# 5-leds.net
KiCad netlist of a schematic drawn in EAGLE
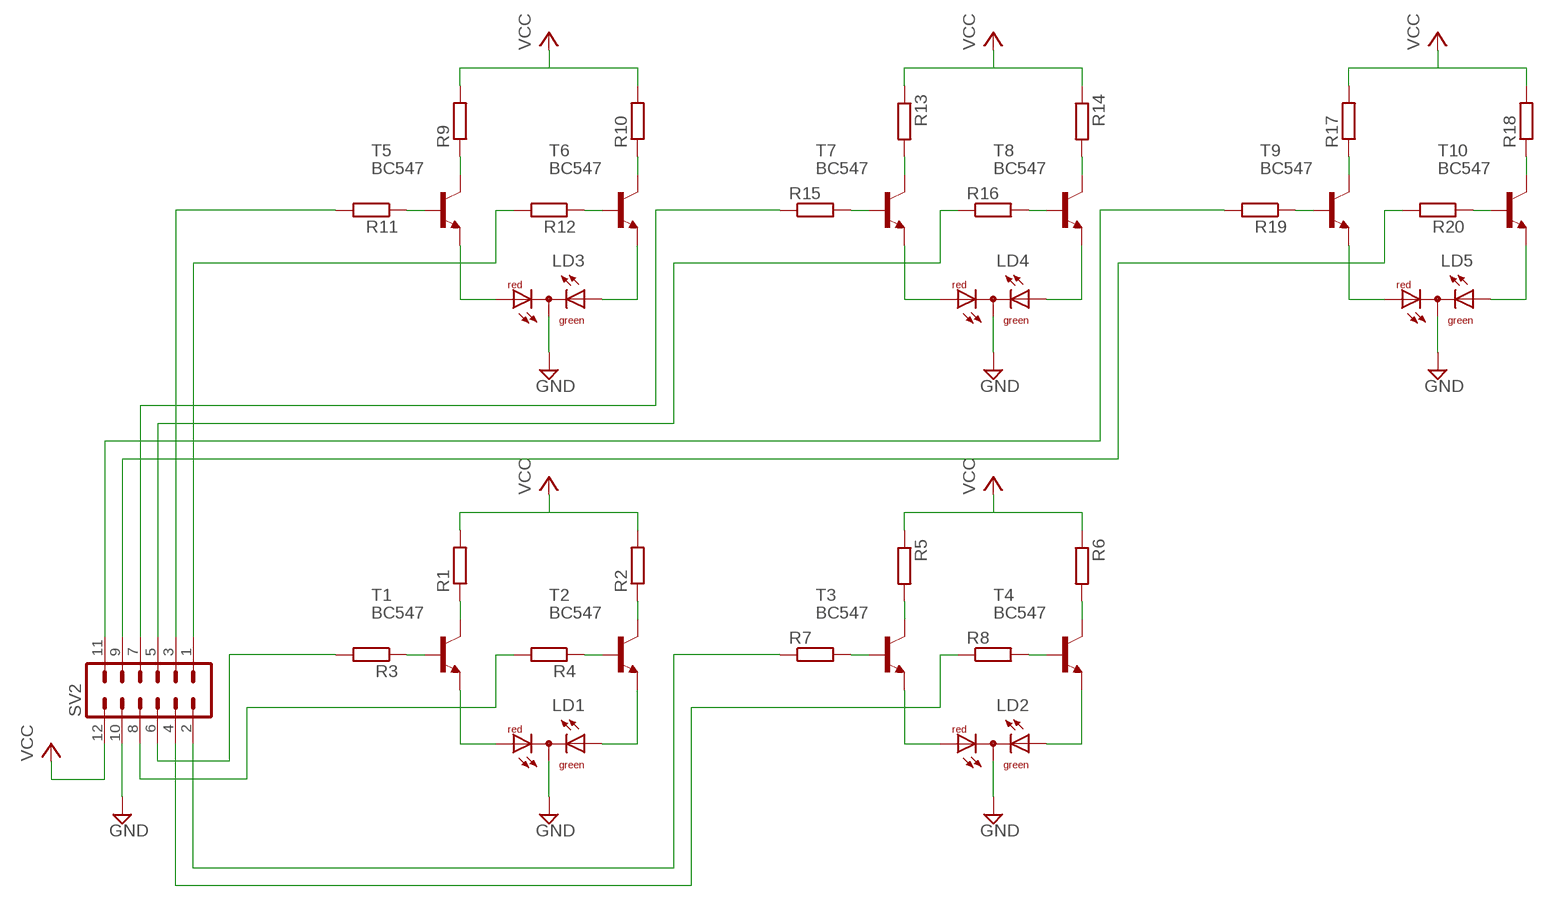
[diagram p0: schematic, sheet 1]

(export (version "E")
  (design (tool "Eeschema 10.0.6"))
  (components
    (comp (ref "LD1")
      (value "DUOLED-RG-C")
      (footprint "eagle-import:DUOLED-C-5MM")
      (libsource (lib "eagle-import") (part "DUOLED-RG-C"))
    )
    (comp (ref "LD2")
      (value "DUOLED-RG-C")
      (footprint "eagle-import:DUOLED-C-5MM")
      (libsource (lib "eagle-import") (part "DUOLED-RG-C"))
    )
    (comp (ref "LD3")
      (value "DUOLED-RG-C")
      (footprint "eagle-import:DUOLED-C-5MM")
      (libsource (lib "eagle-import") (part "DUOLED-RG-C"))
    )
    (comp (ref "LD4")
      (value "DUOLED-RG-C")
      (footprint "eagle-import:DUOLED-C-5MM")
      (libsource (lib "eagle-import") (part "DUOLED-RG-C"))
    )
    (comp (ref "LD5")
      (value "DUOLED-RG-C")
      (footprint "eagle-import:DUOLED-C-5MM")
      (libsource (lib "eagle-import") (part "DUOLED-RG-C"))
    )
    (comp (ref "R1")
      (value "R-EU_0207/7")
      (footprint "eagle-import:0207_7")
      (libsource (lib "eagle-import") (part "R-EU_0207/7"))
    )
    (comp (ref "R2")
      (value "R-EU_0207/7")
      (footprint "eagle-import:0207_7")
      (libsource (lib "eagle-import") (part "R-EU_0207/7"))
    )
    (comp (ref "R3")
      (value "R-EU_0207/7")
      (footprint "eagle-import:0207_7")
      (libsource (lib "eagle-import") (part "R-EU_0207/7"))
    )
    (comp (ref "R4")
      (value "R-EU_0207/7")
      (footprint "eagle-import:0207_7")
      (libsource (lib "eagle-import") (part "R-EU_0207/7"))
    )
    (comp (ref "R5")
      (value "R-EU_0207/7")
      (footprint "eagle-import:0207_7")
      (libsource (lib "eagle-import") (part "R-EU_0207/7"))
    )
    (comp (ref "R6")
      (value "R-EU_0207/7")
      (footprint "eagle-import:0207_7")
      (libsource (lib "eagle-import") (part "R-EU_0207/7"))
    )
    (comp (ref "R7")
      (value "R-EU_0207/7")
      (footprint "eagle-import:0207_7")
      (libsource (lib "eagle-import") (part "R-EU_0207/7"))
    )
    (comp (ref "R8")
      (value "R-EU_0207/7")
      (footprint "eagle-import:0207_7")
      (libsource (lib "eagle-import") (part "R-EU_0207/7"))
    )
    (comp (ref "R9")
      (value "R-EU_0207/7")
      (footprint "eagle-import:0207_7")
      (libsource (lib "eagle-import") (part "R-EU_0207/7"))
    )
    (comp (ref "R10")
      (value "R-EU_0207/7")
      (footprint "eagle-import:0207_7")
      (libsource (lib "eagle-import") (part "R-EU_0207/7"))
    )
    (comp (ref "R11")
      (value "R-EU_0207/7")
      (footprint "eagle-import:0207_7")
      (libsource (lib "eagle-import") (part "R-EU_0207/7"))
    )
    (comp (ref "R12")
      (value "R-EU_0207/7")
      (footprint "eagle-import:0207_7")
      (libsource (lib "eagle-import") (part "R-EU_0207/7"))
    )
    (comp (ref "R13")
      (value "R-EU_0207/7")
      (footprint "eagle-import:0207_7")
      (libsource (lib "eagle-import") (part "R-EU_0207/7"))
    )
    (comp (ref "R14")
      (value "R-EU_0207/7")
      (footprint "eagle-import:0207_7")
      (libsource (lib "eagle-import") (part "R-EU_0207/7"))
    )
    (comp (ref "R15")
      (value "R-EU_0207/7")
      (footprint "eagle-import:0207_7")
      (libsource (lib "eagle-import") (part "R-EU_0207/7"))
    )
    (comp (ref "R16")
      (value "R-EU_0207/7")
      (footprint "eagle-import:0207_7")
      (libsource (lib "eagle-import") (part "R-EU_0207/7"))
    )
    (comp (ref "R17")
      (value "R-EU_0207/7")
      (footprint "eagle-import:0207_7")
      (libsource (lib "eagle-import") (part "R-EU_0207/7"))
    )
    (comp (ref "R18")
      (value "R-EU_0207/7")
      (footprint "eagle-import:0207_7")
      (libsource (lib "eagle-import") (part "R-EU_0207/7"))
    )
    (comp (ref "R19")
      (value "R-EU_0207/7")
      (footprint "eagle-import:0207_7")
      (libsource (lib "eagle-import") (part "R-EU_0207/7"))
    )
    (comp (ref "R20")
      (value "R-EU_0207/7")
      (footprint "eagle-import:0207_7")
      (libsource (lib "eagle-import") (part "R-EU_0207/7"))
    )
    (comp (ref "SV2")
      (value "MA06-2")
      (footprint "eagle-import:MA06-2")
      (libsource (lib "eagle-import") (part "MA06-2"))
    )
    (comp (ref "T1")
      (value "BC547")
      (footprint "eagle-import:TO92")
      (libsource (lib "eagle-import") (part "BC547"))
    )
    (comp (ref "T2")
      (value "BC547")
      (footprint "eagle-import:TO92")
      (libsource (lib "eagle-import") (part "BC547"))
    )
    (comp (ref "T3")
      (value "BC547")
      (footprint "eagle-import:TO92")
      (libsource (lib "eagle-import") (part "BC547"))
    )
    (comp (ref "T4")
      (value "BC547")
      (footprint "eagle-import:TO92")
      (libsource (lib "eagle-import") (part "BC547"))
    )
    (comp (ref "T5")
      (value "BC547")
      (footprint "eagle-import:TO92")
      (libsource (lib "eagle-import") (part "BC547"))
    )
    (comp (ref "T6")
      (value "BC547")
      (footprint "eagle-import:TO92")
      (libsource (lib "eagle-import") (part "BC547"))
    )
    (comp (ref "T7")
      (value "BC547")
      (footprint "eagle-import:TO92")
      (libsource (lib "eagle-import") (part "BC547"))
    )
    (comp (ref "T8")
      (value "BC547")
      (footprint "eagle-import:TO92")
      (libsource (lib "eagle-import") (part "BC547"))
    )
    (comp (ref "T9")
      (value "BC547")
      (footprint "eagle-import:TO92")
      (libsource (lib "eagle-import") (part "BC547"))
    )
    (comp (ref "T10")
      (value "BC547")
      (footprint "eagle-import:TO92")
      (libsource (lib "eagle-import") (part "BC547"))
    )
  )
  (nets
    (net (code "1") (name "GND") (class "Default")
      (node (ref "LD1") (pin "C") (pinfunction "C_C") (pintype "passive"))
      (node (ref "LD2") (pin "C") (pinfunction "C_C") (pintype "passive"))
      (node (ref "LD3") (pin "C") (pinfunction "C_C") (pintype "passive"))
      (node (ref "LD4") (pin "C") (pinfunction "C_C") (pintype "passive"))
      (node (ref "LD5") (pin "C") (pinfunction "C_C") (pintype "passive"))
      (node (ref "SV2") (pin "10") (pinfunction "10_10") (pintype "passive"))
    )
    (net (code "2") (name "Net-(LD1-AG)") (class "Default")
      (node (ref "LD1") (pin "AX") (pinfunction "AG_AX") (pintype "passive"))
      (node (ref "T2") (pin "1") (pinfunction "E_1") (pintype "passive"))
    )
    (net (code "3") (name "Net-(LD2-AG)") (class "Default")
      (node (ref "LD2") (pin "AX") (pinfunction "AG_AX") (pintype "passive"))
      (node (ref "T4") (pin "1") (pinfunction "E_1") (pintype "passive"))
    )
    (net (code "4") (name "Net-(LD3-AG)") (class "Default")
      (node (ref "LD3") (pin "AX") (pinfunction "AG_AX") (pintype "passive"))
      (node (ref "T6") (pin "1") (pinfunction "E_1") (pintype "passive"))
    )
    (net (code "5") (name "Net-(LD4-AG)") (class "Default")
      (node (ref "LD4") (pin "AX") (pinfunction "AG_AX") (pintype "passive"))
      (node (ref "T8") (pin "1") (pinfunction "E_1") (pintype "passive"))
    )
    (net (code "6") (name "Net-(LD5-AG)") (class "Default")
      (node (ref "LD5") (pin "AX") (pinfunction "AG_AX") (pintype "passive"))
      (node (ref "T10") (pin "1") (pinfunction "E_1") (pintype "passive"))
    )
    (net (code "7") (name "Net-(R3-Pad2)") (class "Default")
      (node (ref "R3") (pin "2") (pinfunction "2_2") (pintype "passive"))
      (node (ref "SV2") (pin "6") (pinfunction "6_6") (pintype "passive"))
    )
    (net (code "8") (name "Net-(R4-Pad2)") (class "Default")
      (node (ref "R4") (pin "2") (pinfunction "2_2") (pintype "passive"))
      (node (ref "SV2") (pin "8") (pinfunction "8_8") (pintype "passive"))
    )
    (net (code "9") (name "Net-(R7-Pad1)") (class "Default")
      (node (ref "R7") (pin "1") (pinfunction "1_1") (pintype "passive"))
      (node (ref "SV2") (pin "2") (pinfunction "2_2") (pintype "passive"))
    )
    (net (code "10") (name "Net-(R8-Pad1)") (class "Default")
      (node (ref "R8") (pin "1") (pinfunction "1_1") (pintype "passive"))
      (node (ref "SV2") (pin "4") (pinfunction "4_4") (pintype "passive"))
    )
    (net (code "11") (name "Net-(R11-Pad2)") (class "Default")
      (node (ref "R11") (pin "2") (pinfunction "2_2") (pintype "passive"))
      (node (ref "SV2") (pin "3") (pinfunction "3_3") (pintype "passive"))
    )
    (net (code "12") (name "Net-(R12-Pad2)") (class "Default")
      (node (ref "R12") (pin "2") (pinfunction "2_2") (pintype "passive"))
      (node (ref "SV2") (pin "1") (pinfunction "1_1") (pintype "passive"))
    )
    (net (code "13") (name "Net-(R15-Pad1)") (class "Default")
      (node (ref "R15") (pin "1") (pinfunction "1_1") (pintype "passive"))
      (node (ref "SV2") (pin "7") (pinfunction "7_7") (pintype "passive"))
    )
    (net (code "14") (name "Net-(R16-Pad1)") (class "Default")
      (node (ref "R16") (pin "1") (pinfunction "1_1") (pintype "passive"))
      (node (ref "SV2") (pin "5") (pinfunction "5_5") (pintype "passive"))
    )
    (net (code "15") (name "Net-(R19-Pad2)") (class "Default")
      (node (ref "R19") (pin "2") (pinfunction "2_2") (pintype "passive"))
      (node (ref "SV2") (pin "11") (pinfunction "11_11") (pintype "passive"))
    )
    (net (code "16") (name "Net-(R20-Pad2)") (class "Default")
      (node (ref "R20") (pin "2") (pinfunction "2_2") (pintype "passive"))
      (node (ref "SV2") (pin "9") (pinfunction "9_9") (pintype "passive"))
    )
    (net (code "17") (name "Net-(T1-B)") (class "Default")
      (node (ref "R3") (pin "1") (pinfunction "1_1") (pintype "passive"))
      (node (ref "T1") (pin "2") (pinfunction "B_2") (pintype "passive"))
    )
    (net (code "18") (name "Net-(T1-C)") (class "Default")
      (node (ref "R1") (pin "1") (pinfunction "1_1") (pintype "passive"))
      (node (ref "T1") (pin "3") (pinfunction "C_3") (pintype "passive"))
    )
    (net (code "19") (name "Net-(T1-E)") (class "Default")
      (node (ref "LD1") (pin "AR") (pinfunction "AR_AR") (pintype "passive"))
      (node (ref "T1") (pin "1") (pinfunction "E_1") (pintype "passive"))
    )
    (net (code "20") (name "Net-(T2-B)") (class "Default")
      (node (ref "R4") (pin "1") (pinfunction "1_1") (pintype "passive"))
      (node (ref "T2") (pin "2") (pinfunction "B_2") (pintype "passive"))
    )
    (net (code "21") (name "Net-(T2-C)") (class "Default")
      (node (ref "R2") (pin "1") (pinfunction "1_1") (pintype "passive"))
      (node (ref "T2") (pin "3") (pinfunction "C_3") (pintype "passive"))
    )
    (net (code "22") (name "Net-(T3-B)") (class "Default")
      (node (ref "R7") (pin "2") (pinfunction "2_2") (pintype "passive"))
      (node (ref "T3") (pin "2") (pinfunction "B_2") (pintype "passive"))
    )
    (net (code "23") (name "Net-(T3-C)") (class "Default")
      (node (ref "R5") (pin "2") (pinfunction "2_2") (pintype "passive"))
      (node (ref "T3") (pin "3") (pinfunction "C_3") (pintype "passive"))
    )
    (net (code "24") (name "Net-(T3-E)") (class "Default")
      (node (ref "LD2") (pin "AR") (pinfunction "AR_AR") (pintype "passive"))
      (node (ref "T3") (pin "1") (pinfunction "E_1") (pintype "passive"))
    )
    (net (code "25") (name "Net-(T4-B)") (class "Default")
      (node (ref "R8") (pin "2") (pinfunction "2_2") (pintype "passive"))
      (node (ref "T4") (pin "2") (pinfunction "B_2") (pintype "passive"))
    )
    (net (code "26") (name "Net-(T4-C)") (class "Default")
      (node (ref "R6") (pin "2") (pinfunction "2_2") (pintype "passive"))
      (node (ref "T4") (pin "3") (pinfunction "C_3") (pintype "passive"))
    )
    (net (code "27") (name "Net-(T5-B)") (class "Default")
      (node (ref "R11") (pin "1") (pinfunction "1_1") (pintype "passive"))
      (node (ref "T5") (pin "2") (pinfunction "B_2") (pintype "passive"))
    )
    (net (code "28") (name "Net-(T5-C)") (class "Default")
      (node (ref "R9") (pin "1") (pinfunction "1_1") (pintype "passive"))
      (node (ref "T5") (pin "3") (pinfunction "C_3") (pintype "passive"))
    )
    (net (code "29") (name "Net-(T5-E)") (class "Default")
      (node (ref "LD3") (pin "AR") (pinfunction "AR_AR") (pintype "passive"))
      (node (ref "T5") (pin "1") (pinfunction "E_1") (pintype "passive"))
    )
    (net (code "30") (name "Net-(T6-B)") (class "Default")
      (node (ref "R12") (pin "1") (pinfunction "1_1") (pintype "passive"))
      (node (ref "T6") (pin "2") (pinfunction "B_2") (pintype "passive"))
    )
    (net (code "31") (name "Net-(T6-C)") (class "Default")
      (node (ref "R10") (pin "1") (pinfunction "1_1") (pintype "passive"))
      (node (ref "T6") (pin "3") (pinfunction "C_3") (pintype "passive"))
    )
    (net (code "32") (name "Net-(T7-B)") (class "Default")
      (node (ref "R15") (pin "2") (pinfunction "2_2") (pintype "passive"))
      (node (ref "T7") (pin "2") (pinfunction "B_2") (pintype "passive"))
    )
    (net (code "33") (name "Net-(T7-C)") (class "Default")
      (node (ref "R13") (pin "2") (pinfunction "2_2") (pintype "passive"))
      (node (ref "T7") (pin "3") (pinfunction "C_3") (pintype "passive"))
    )
    (net (code "34") (name "Net-(T7-E)") (class "Default")
      (node (ref "LD4") (pin "AR") (pinfunction "AR_AR") (pintype "passive"))
      (node (ref "T7") (pin "1") (pinfunction "E_1") (pintype "passive"))
    )
    (net (code "35") (name "Net-(T8-B)") (class "Default")
      (node (ref "R16") (pin "2") (pinfunction "2_2") (pintype "passive"))
      (node (ref "T8") (pin "2") (pinfunction "B_2") (pintype "passive"))
    )
    (net (code "36") (name "Net-(T8-C)") (class "Default")
      (node (ref "R14") (pin "2") (pinfunction "2_2") (pintype "passive"))
      (node (ref "T8") (pin "3") (pinfunction "C_3") (pintype "passive"))
    )
    (net (code "37") (name "Net-(T9-B)") (class "Default")
      (node (ref "R19") (pin "1") (pinfunction "1_1") (pintype "passive"))
      (node (ref "T9") (pin "2") (pinfunction "B_2") (pintype "passive"))
    )
    (net (code "38") (name "Net-(T9-C)") (class "Default")
      (node (ref "R17") (pin "1") (pinfunction "1_1") (pintype "passive"))
      (node (ref "T9") (pin "3") (pinfunction "C_3") (pintype "passive"))
    )
    (net (code "39") (name "Net-(T9-E)") (class "Default")
      (node (ref "LD5") (pin "AR") (pinfunction "AR_AR") (pintype "passive"))
      (node (ref "T9") (pin "1") (pinfunction "E_1") (pintype "passive"))
    )
    (net (code "40") (name "Net-(T10-B)") (class "Default")
      (node (ref "R20") (pin "1") (pinfunction "1_1") (pintype "passive"))
      (node (ref "T10") (pin "2") (pinfunction "B_2") (pintype "passive"))
    )
    (net (code "41") (name "Net-(T10-C)") (class "Default")
      (node (ref "R18") (pin "1") (pinfunction "1_1") (pintype "passive"))
      (node (ref "T10") (pin "3") (pinfunction "C_3") (pintype "passive"))
    )
    (net (code "42") (name "VCC") (class "Default")
      (node (ref "R1") (pin "2") (pinfunction "2_2") (pintype "passive"))
      (node (ref "R10") (pin "2") (pinfunction "2_2") (pintype "passive"))
      (node (ref "R13") (pin "1") (pinfunction "1_1") (pintype "passive"))
      (node (ref "R14") (pin "1") (pinfunction "1_1") (pintype "passive"))
      (node (ref "R17") (pin "2") (pinfunction "2_2") (pintype "passive"))
      (node (ref "R18") (pin "2") (pinfunction "2_2") (pintype "passive"))
      (node (ref "R2") (pin "2") (pinfunction "2_2") (pintype "passive"))
      (node (ref "R5") (pin "1") (pinfunction "1_1") (pintype "passive"))
      (node (ref "R6") (pin "1") (pinfunction "1_1") (pintype "passive"))
      (node (ref "R9") (pin "2") (pinfunction "2_2") (pintype "passive"))
      (node (ref "SV2") (pin "12") (pinfunction "12_12") (pintype "passive"))
    )
  )
)
